# AVRProg.net
KiCad netlist of a schematic drawn in EAGLE
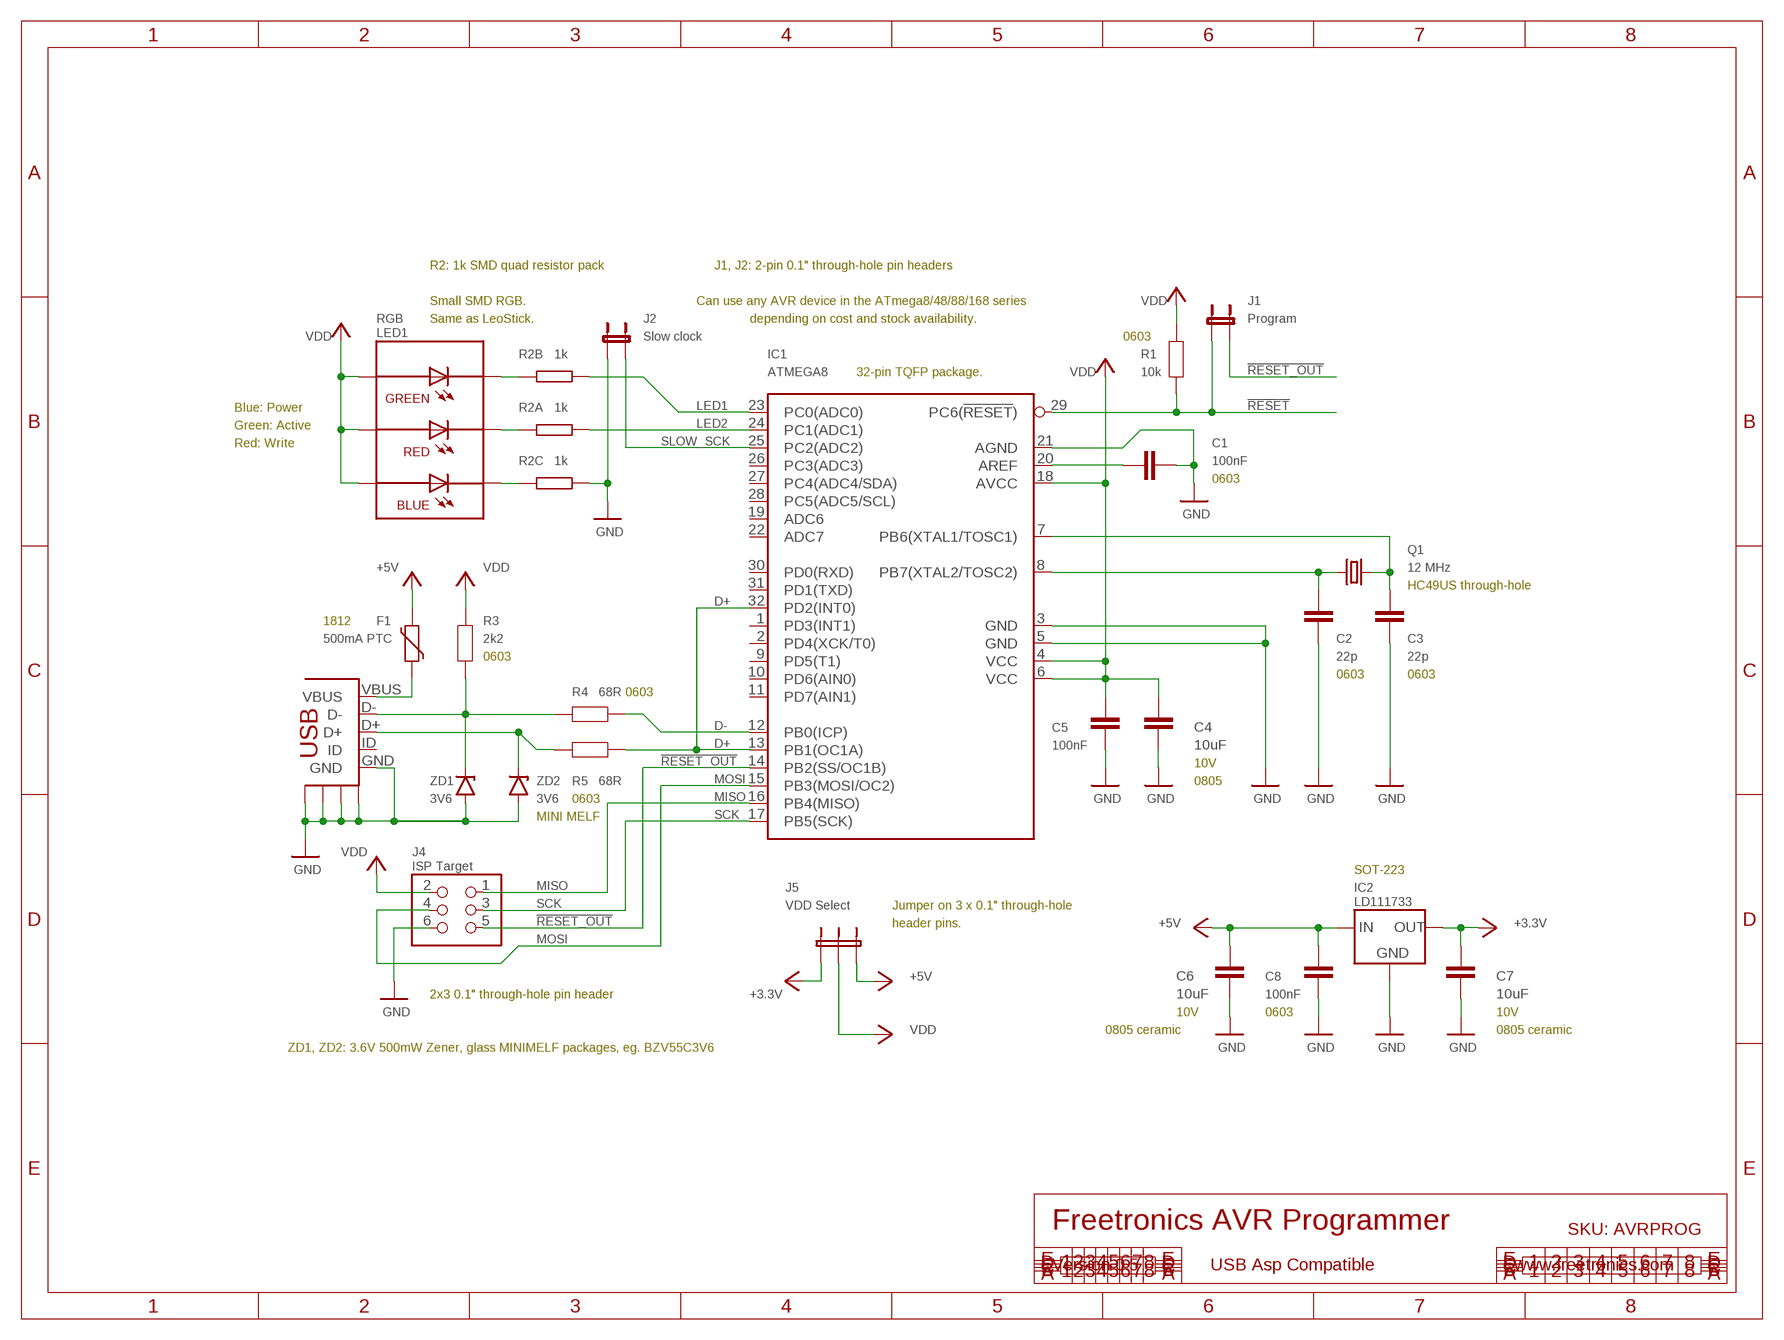
[diagram p0: schematic, sheet 1]

(export (version "E")
  (design (tool "Eeschema 10.0.6"))
  (components
    (comp (ref "C1")
      (value "100nF")
      (footprint "eagle-import:0603")
      (libsource (lib "eagle-import") (part "CAP0603"))
    )
    (comp (ref "C2")
      (value "22p")
      (footprint "eagle-import:0603")
      (libsource (lib "eagle-import") (part "CAP0603"))
    )
    (comp (ref "C3")
      (value "22p")
      (footprint "eagle-import:0603")
      (libsource (lib "eagle-import") (part "CAP0603"))
    )
    (comp (ref "C4")
      (value "10uF")
      (footprint "eagle-import:C0805")
      (libsource (lib "eagle-import") (part "C-EUC0805"))
    )
    (comp (ref "C5")
      (value "100nF")
      (footprint "eagle-import:0603")
      (libsource (lib "eagle-import") (part "CAP0603"))
    )
    (comp (ref "C6")
      (value "10uF")
      (footprint "eagle-import:C0805")
      (libsource (lib "eagle-import") (part "C-EUC0805"))
    )
    (comp (ref "C7")
      (value "10uF")
      (footprint "eagle-import:C0805")
      (libsource (lib "eagle-import") (part "C-EUC0805"))
    )
    (comp (ref "C8")
      (value "100nF")
      (footprint "eagle-import:0603")
      (libsource (lib "eagle-import") (part "CAP0603"))
    )
    (comp (ref "F1")
      (value "500mA PTC")
      (footprint "eagle-import:1812")
      (libsource (lib "eagle-import") (part "PTC"))
    )
    (comp (ref "IC1")
      (value "ATMEGA8")
      (footprint "eagle-import:TQFP32-08")
      (libsource (lib "eagle-import") (part "ATMEGA168"))
    )
    (comp (ref "IC2")
      (value "LD111733")
      (footprint "eagle-import:SOT-223")
      (libsource (lib "eagle-import") (part "LD1117-FIXED"))
    )
    (comp (ref "J1")
      (value "Program")
      (footprint "eagle-import:HEADER_1X02")
      (libsource (lib "eagle-import") (part "JUMPER_PTH"))
    )
    (comp (ref "J2")
      (value "Slow clock")
      (footprint "eagle-import:HEADER_1X02")
      (libsource (lib "eagle-import") (part "JUMPER_PTH"))
    )
    (comp (ref "J3")
      (value "USB")
      (footprint "eagle-import:USB-MINIB-FT")
      (libsource (lib "eagle-import") (part "USB-FT"))
    )
    (comp (ref "J4")
      (value "ISP Target")
      (footprint "eagle-import:HEADER_2X3")
      (libsource (lib "eagle-import") (part "HEADER_2X3"))
    )
    (comp (ref "J5")
      (value "VDD Select")
      (footprint "eagle-import:JUMPER_SPDT")
      (libsource (lib "eagle-import") (part "JUMPER_SPDT"))
    )
    (comp (ref "LED1")
      (value "RGB")
      (footprint "eagle-import:19-337")
      (libsource (lib "eagle-import") (part "RGBLEDSMT"))
    )
    (comp (ref "Q1")
      (value "12 MHz")
      (footprint "eagle-import:HC49US")
      (libsource (lib "eagle-import") (part "CRYSTALHC49US"))
    )
    (comp (ref "R1")
      (value "10k")
      (footprint "eagle-import:0603")
      (libsource (lib "eagle-import") (part "RESISTOR0603"))
    )
    (comp (ref "R2")
      (value "1k")
      (footprint "eagle-import:CAY16")
      (libsource (lib "eagle-import") (part "CAY16"))
    )
    (comp (ref "R3")
      (value "2k2")
      (footprint "eagle-import:0603")
      (libsource (lib "eagle-import") (part "RESISTOR0603"))
    )
    (comp (ref "R4")
      (value "68R")
      (footprint "eagle-import:0603")
      (libsource (lib "eagle-import") (part "RESISTOR0603"))
    )
    (comp (ref "R5")
      (value "68R")
      (footprint "eagle-import:0603")
      (libsource (lib "eagle-import") (part "RESISTOR0603"))
    )
    (comp (ref "ZD1")
      (value "3V6")
      (footprint "eagle-import:MINIMELF")
      (libsource (lib "eagle-import") (part "ZENERMINIMELF"))
    )
    (comp (ref "ZD2")
      (value "3V6")
      (footprint "eagle-import:MINIMELF")
      (libsource (lib "eagle-import") (part "ZENERMINIMELF"))
    )
  )
  (nets
    (net (code "1") (name "+3.3V") (class "Default")
      (node (ref "C7") (pin "1") (pinfunction "1_1") (pintype "passive"))
      (node (ref "IC2") (pin "2") (pinfunction "OUT_2") (pintype "power_in"))
      (node (ref "IC2") (pin "4") (pinfunction "OUT_4") (pintype "power_in"))
      (node (ref "J5") (pin "1") (pinfunction "1_1") (pintype "passive"))
    )
    (net (code "2") (name "+5V") (class "Default")
      (node (ref "C6") (pin "1") (pinfunction "1_1") (pintype "passive"))
      (node (ref "C8") (pin "1") (pinfunction "1_1") (pintype "passive"))
      (node (ref "F1") (pin "2") (pinfunction "P$2_2") (pintype "bidirectional"))
      (node (ref "IC2") (pin "3") (pinfunction "IN_3") (pintype "input"))
      (node (ref "J5") (pin "3") (pinfunction "3_3") (pintype "passive"))
    )
    (net (code "3") (name "/D+") (class "Default")
      (node (ref "IC1") (pin "13") (pinfunction "PB1(OC1A)_13") (pintype "bidirectional"))
      (node (ref "IC1") (pin "32") (pinfunction "PD2(INT0)_32") (pintype "bidirectional"))
      (node (ref "R5") (pin "1") (pinfunction "1_1") (pintype "passive"))
    )
    (net (code "4") (name "/D-") (class "Default")
      (node (ref "IC1") (pin "12") (pinfunction "PB0(ICP)_12") (pintype "bidirectional"))
      (node (ref "R4") (pin "1") (pinfunction "1_1") (pintype "passive"))
    )
    (net (code "5") (name "/LED1") (class "Default")
      (node (ref "IC1") (pin "23") (pinfunction "PC0(ADC0)_23") (pintype "bidirectional"))
      (node (ref "R2") (pin "2") (pinfunction "1_2") (pintype "passive"))
    )
    (net (code "6") (name "/LED2") (class "Default")
      (node (ref "IC1") (pin "24") (pinfunction "PC1(ADC1)_24") (pintype "bidirectional"))
      (node (ref "R2") (pin "1") (pinfunction "1_1") (pintype "passive"))
    )
    (net (code "7") (name "/MISO") (class "Default")
      (node (ref "IC1") (pin "16") (pinfunction "PB4(MISO)_16") (pintype "bidirectional"))
      (node (ref "J4") (pin "1") (pinfunction "1_1") (pintype "passive"))
    )
    (net (code "8") (name "/MOSI") (class "Default")
      (node (ref "IC1") (pin "15") (pinfunction "PB3(MOSI/OC2)_15") (pintype "bidirectional"))
      (node (ref "J4") (pin "4") (pinfunction "4_4") (pintype "passive"))
    )
    (net (code "9") (name "/SCK") (class "Default")
      (node (ref "IC1") (pin "17") (pinfunction "PB5(SCK)_17") (pintype "bidirectional"))
      (node (ref "J4") (pin "3") (pinfunction "3_3") (pintype "passive"))
    )
    (net (code "10") (name "/SLOW_SCK") (class "Default")
      (node (ref "IC1") (pin "25") (pinfunction "PC2(ADC2)_25") (pintype "bidirectional"))
      (node (ref "J2") (pin "2") (pinfunction "2_2") (pintype "passive"))
    )
    (net (code "11") (name "/~{RESET_OUT}") (class "Default")
      (node (ref "IC1") (pin "14") (pinfunction "PB2(SS/OC1B)_14") (pintype "bidirectional"))
      (node (ref "J1") (pin "2") (pinfunction "2_2") (pintype "passive"))
      (node (ref "J4") (pin "5") (pinfunction "5_5") (pintype "passive"))
    )
    (net (code "12") (name "/~{RESET}") (class "Default")
      (node (ref "IC1") (pin "29") (pinfunction "PC6(~{RESET})_29") (pintype "bidirectional"))
      (node (ref "J1") (pin "1") (pinfunction "1_1") (pintype "passive"))
      (node (ref "R1") (pin "1") (pinfunction "1_1") (pintype "passive"))
    )
    (net (code "13") (name "GND") (class "Default")
      (node (ref "C1") (pin "2") (pinfunction "2_2") (pintype "passive"))
      (node (ref "C2") (pin "1") (pinfunction "1_1") (pintype "passive"))
      (node (ref "C3") (pin "1") (pinfunction "1_1") (pintype "passive"))
      (node (ref "C4") (pin "2") (pinfunction "2_2") (pintype "passive"))
      (node (ref "C5") (pin "2") (pinfunction "2_2") (pintype "passive"))
      (node (ref "C6") (pin "2") (pinfunction "2_2") (pintype "passive"))
      (node (ref "C7") (pin "2") (pinfunction "2_2") (pintype "passive"))
      (node (ref "C8") (pin "2") (pinfunction "2_2") (pintype "passive"))
      (node (ref "IC1") (pin "21") (pinfunction "AGND_21") (pintype "bidirectional"))
      (node (ref "IC1") (pin "3") (pinfunction "GND_3") (pintype "bidirectional"))
      (node (ref "IC1") (pin "5") (pinfunction "GND_5") (pintype "bidirectional"))
      (node (ref "IC2") (pin "1") (pinfunction "GND_1") (pintype "input"))
      (node (ref "J2") (pin "1") (pinfunction "1_1") (pintype "passive"))
      (node (ref "J3") (pin "GND") (pinfunction "GND_GND") (pintype "bidirectional"))
      (node (ref "J3") (pin "SH1") (pinfunction "SH$1_SH1") (pintype "passive"))
      (node (ref "J3") (pin "SH2") (pinfunction "SH$2_SH2") (pintype "passive"))
      (node (ref "J3") (pin "SH3") (pinfunction "SH$3_SH3") (pintype "passive"))
      (node (ref "J3") (pin "SH4") (pinfunction "SH$4_SH4") (pintype "passive"))
      (node (ref "J4") (pin "6") (pinfunction "6_6") (pintype "passive"))
      (node (ref "R2") (pin "3") (pinfunction "1_3") (pintype "passive"))
      (node (ref "ZD1") (pin "A") (pinfunction "A_A") (pintype "passive"))
      (node (ref "ZD2") (pin "A") (pinfunction "A_A") (pintype "passive"))
    )
    (net (code "14") (name "Net-(F1-P$1)") (class "Default")
      (node (ref "F1") (pin "1") (pinfunction "P$1_1") (pintype "bidirectional"))
      (node (ref "J3") (pin "VBUS") (pinfunction "VBUS_VBUS") (pintype "bidirectional"))
    )
    (net (code "15") (name "Net-(IC1-AREF)") (class "Default")
      (node (ref "C1") (pin "1") (pinfunction "1_1") (pintype "passive"))
      (node (ref "IC1") (pin "20") (pinfunction "AREF_20") (pintype "bidirectional"))
    )
    (net (code "16") (name "Net-(IC1-PB6(XTAL1{slash}TOSC1))") (class "Default")
      (node (ref "C3") (pin "2") (pinfunction "2_2") (pintype "passive"))
      (node (ref "IC1") (pin "7") (pinfunction "PB6(XTAL1/TOSC1)_7") (pintype "bidirectional"))
      (node (ref "Q1") (pin "2") (pinfunction "2_2") (pintype "passive"))
    )
    (net (code "17") (name "Net-(IC1-PB7(XTAL2{slash}TOSC2))") (class "Default")
      (node (ref "C2") (pin "2") (pinfunction "2_2") (pintype "passive"))
      (node (ref "IC1") (pin "8") (pinfunction "PB7(XTAL2/TOSC2)_8") (pintype "bidirectional"))
      (node (ref "Q1") (pin "1") (pinfunction "1_1") (pintype "passive"))
    )
    (net (code "18") (name "Net-(J3-PadD+)") (class "Default")
      (node (ref "J3") (pin "D+") (pinfunction "D+_D+") (pintype "bidirectional"))
      (node (ref "R5") (pin "2") (pinfunction "2_2") (pintype "passive"))
      (node (ref "ZD2") (pin "K") (pinfunction "K_K") (pintype "passive"))
    )
    (net (code "19") (name "Net-(J3-PadD-)") (class "Default")
      (node (ref "J3") (pin "D-") (pinfunction "D-_D-") (pintype "bidirectional"))
      (node (ref "R3") (pin "1") (pinfunction "1_1") (pintype "passive"))
      (node (ref "R4") (pin "2") (pinfunction "2_2") (pintype "passive"))
      (node (ref "ZD1") (pin "K") (pinfunction "K_K") (pintype "passive"))
    )
    (net (code "20") (name "Net-(LED1-C-B)") (class "Default")
      (node (ref "LED1") (pin "1") (pinfunction "C-B_1") (pintype "passive"))
      (node (ref "R2") (pin "6") (pinfunction "2_6") (pintype "passive"))
    )
    (net (code "21") (name "Net-(LED1-C-G)") (class "Default")
      (node (ref "LED1") (pin "3") (pinfunction "C-G_3") (pintype "passive"))
      (node (ref "R2") (pin "7") (pinfunction "2_7") (pintype "passive"))
    )
    (net (code "22") (name "Net-(LED1-C-R)") (class "Default")
      (node (ref "LED1") (pin "2") (pinfunction "C-R_2") (pintype "passive"))
      (node (ref "R2") (pin "8") (pinfunction "2_8") (pintype "passive"))
    )
    (net (code "23") (name "VDD") (class "Default")
      (node (ref "C4") (pin "1") (pinfunction "1_1") (pintype "passive"))
      (node (ref "C5") (pin "1") (pinfunction "1_1") (pintype "passive"))
      (node (ref "IC1") (pin "18") (pinfunction "AVCC_18") (pintype "bidirectional"))
      (node (ref "IC1") (pin "4") (pinfunction "VCC_4") (pintype "bidirectional"))
      (node (ref "IC1") (pin "6") (pinfunction "VCC_6") (pintype "bidirectional"))
      (node (ref "J4") (pin "2") (pinfunction "2_2") (pintype "passive"))
      (node (ref "J5") (pin "2") (pinfunction "2_2") (pintype "passive"))
      (node (ref "LED1") (pin "4") (pinfunction "A-B_4") (pintype "passive"))
      (node (ref "LED1") (pin "5") (pinfunction "A-R_5") (pintype "passive"))
      (node (ref "LED1") (pin "6") (pinfunction "A-G_6") (pintype "passive"))
      (node (ref "R1") (pin "2") (pinfunction "2_2") (pintype "passive"))
      (node (ref "R3") (pin "2") (pinfunction "2_2") (pintype "passive"))
    )
    (net (code "24") (name "unconnected-(IC1-ADC6-Pad19)") (class "Default")
      (node (ref "IC1") (pin "19") (pinfunction "ADC6_19") (pintype "bidirectional"))
    )
    (net (code "25") (name "unconnected-(IC1-ADC7-Pad22)") (class "Default")
      (node (ref "IC1") (pin "22") (pinfunction "ADC7_22") (pintype "bidirectional"))
    )
    (net (code "26") (name "unconnected-(IC1-PC3(ADC3)-Pad26)") (class "Default")
      (node (ref "IC1") (pin "26") (pinfunction "PC3(ADC3)_26") (pintype "bidirectional"))
    )
    (net (code "27") (name "unconnected-(IC1-PC4(ADC4{slash}SDA)-Pad27)") (class "Default")
      (node (ref "IC1") (pin "27") (pinfunction "PC4(ADC4/SDA)_27") (pintype "bidirectional"))
    )
    (net (code "28") (name "unconnected-(IC1-PC5(ADC5{slash}SCL)-Pad28)") (class "Default")
      (node (ref "IC1") (pin "28") (pinfunction "PC5(ADC5/SCL)_28") (pintype "bidirectional"))
    )
    (net (code "29") (name "unconnected-(IC1-PD0(RXD)-Pad30)") (class "Default")
      (node (ref "IC1") (pin "30") (pinfunction "PD0(RXD)_30") (pintype "bidirectional"))
    )
    (net (code "30") (name "unconnected-(IC1-PD1(TXD)-Pad31)") (class "Default")
      (node (ref "IC1") (pin "31") (pinfunction "PD1(TXD)_31") (pintype "bidirectional"))
    )
    (net (code "31") (name "unconnected-(IC1-PD3(INT1)-Pad1)") (class "Default")
      (node (ref "IC1") (pin "1") (pinfunction "PD3(INT1)_1") (pintype "bidirectional"))
    )
    (net (code "32") (name "unconnected-(IC1-PD4(XCK{slash}T0)-Pad2)") (class "Default")
      (node (ref "IC1") (pin "2") (pinfunction "PD4(XCK/T0)_2") (pintype "bidirectional"))
    )
    (net (code "33") (name "unconnected-(IC1-PD5(T1)-Pad9)") (class "Default")
      (node (ref "IC1") (pin "9") (pinfunction "PD5(T1)_9") (pintype "bidirectional"))
    )
    (net (code "34") (name "unconnected-(IC1-PD6(AIN0)-Pad10)") (class "Default")
      (node (ref "IC1") (pin "10") (pinfunction "PD6(AIN0)_10") (pintype "bidirectional"))
    )
    (net (code "35") (name "unconnected-(IC1-PD7(AIN1)-Pad11)") (class "Default")
      (node (ref "IC1") (pin "11") (pinfunction "PD7(AIN1)_11") (pintype "bidirectional"))
    )
    (net (code "36") (name "unconnected-(J3-PadID)") (class "Default")
      (node (ref "J3") (pin "ID") (pinfunction "ID_ID") (pintype "bidirectional"))
    )
  )
)
